# wm8510-dev-board.net
KiCad netlist of a schematic drawn in EAGLE
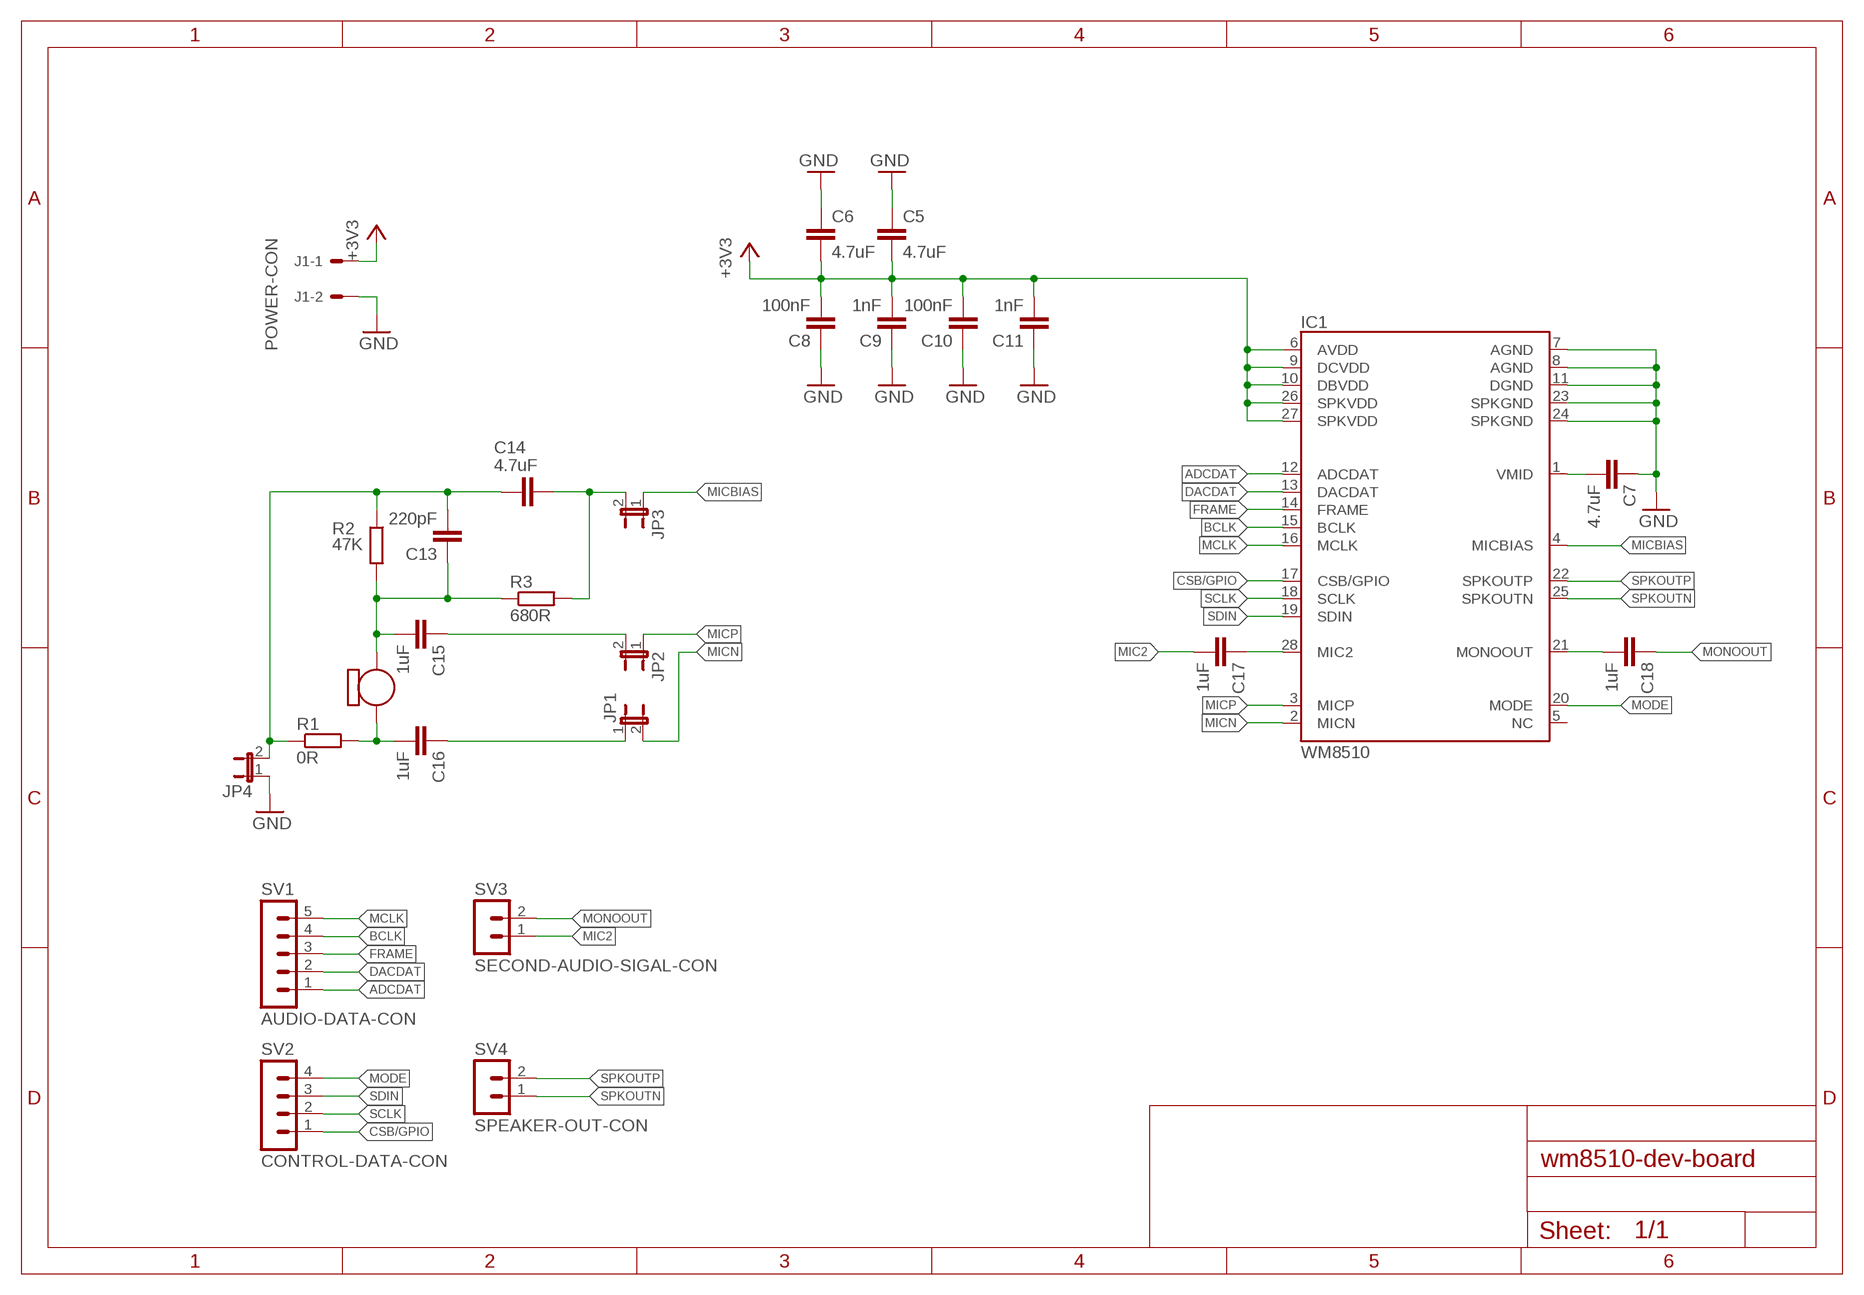
[diagram p0: schematic, sheet 1]

(export (version "E")
  (design (tool "Eeschema 10.0.6"))
  (components
    (comp (ref "C5")
      (value "4.7uF")
      (footprint "eagle-import:C1206")
      (libsource (lib "eagle-import") (part "C-EUC1206"))
    )
    (comp (ref "C6")
      (value "4.7uF")
      (footprint "eagle-import:C1206")
      (libsource (lib "eagle-import") (part "C-EUC1206"))
    )
    (comp (ref "C7")
      (value "4.7uF")
      (footprint "eagle-import:C1206")
      (libsource (lib "eagle-import") (part "C-EUC1206"))
    )
    (comp (ref "C8")
      (value "100nF")
      (footprint "eagle-import:C1206")
      (libsource (lib "eagle-import") (part "C-EUC1206"))
    )
    (comp (ref "C9")
      (value "1nF")
      (footprint "eagle-import:C1206")
      (libsource (lib "eagle-import") (part "C-EUC1206"))
    )
    (comp (ref "C10")
      (value "100nF")
      (footprint "eagle-import:C1206")
      (libsource (lib "eagle-import") (part "C-EUC1206"))
    )
    (comp (ref "C11")
      (value "1nF")
      (footprint "eagle-import:C1206")
      (libsource (lib "eagle-import") (part "C-EUC1206"))
    )
    (comp (ref "C13")
      (value "220pF")
      (footprint "eagle-import:C1206")
      (libsource (lib "eagle-import") (part "C-EUC1206"))
    )
    (comp (ref "C14")
      (value "4.7uF")
      (footprint "eagle-import:C1206")
      (libsource (lib "eagle-import") (part "C-EUC1206"))
    )
    (comp (ref "C15")
      (value "1uF")
      (footprint "eagle-import:C1206")
      (libsource (lib "eagle-import") (part "C-EUC1206"))
    )
    (comp (ref "C16")
      (value "1uF")
      (footprint "eagle-import:C1206")
      (libsource (lib "eagle-import") (part "C-EUC1206"))
    )
    (comp (ref "C17")
      (value "1uF")
      (footprint "eagle-import:C1206")
      (libsource (lib "eagle-import") (part "C-EUC1206"))
    )
    (comp (ref "C18")
      (value "1uF")
      (footprint "eagle-import:C1206")
      (libsource (lib "eagle-import") (part "C-EUC1206"))
    )
    (comp (ref "IC1")
      (value "WM8510")
      (footprint "eagle-import:SSOP28")
      (libsource (lib "eagle-import") (part "WM8510"))
    )
    (comp (ref "J1")
      (value "POWER-CON")
      (footprint "eagle-import:6410-02")
      (libsource (lib "eagle-import") (part "22-?-0227-2021"))
    )
    (comp (ref "JP1")
      (value "JP1E")
      (footprint "eagle-import:JP1")
      (libsource (lib "eagle-import") (part "JP1E"))
    )
    (comp (ref "JP2")
      (value "JP1E")
      (footprint "eagle-import:JP1")
      (libsource (lib "eagle-import") (part "JP1E"))
    )
    (comp (ref "JP3")
      (value "JP1E")
      (footprint "eagle-import:JP1")
      (libsource (lib "eagle-import") (part "JP1E"))
    )
    (comp (ref "JP4")
      (value "JP1E")
      (footprint "eagle-import:JP1")
      (libsource (lib "eagle-import") (part "JP1E"))
    )
    (comp (ref "R1")
      (value "0R")
      (footprint "eagle-import:R1206")
      (libsource (lib "eagle-import") (part "R-EU_R1206"))
    )
    (comp (ref "R2")
      (value "47K")
      (footprint "eagle-import:R1206")
      (libsource (lib "eagle-import") (part "R-EU_R1206"))
    )
    (comp (ref "R3")
      (value "680R")
      (footprint "eagle-import:R1206")
      (libsource (lib "eagle-import") (part "R-EU_R1206"))
    )
    (comp (ref "SV1")
      (value "AUDIO-DATA-CON")
      (footprint "eagle-import:MA05-1")
      (libsource (lib "eagle-import") (part "MA05-1"))
    )
    (comp (ref "SV2")
      (value "CONTROL-DATA-CON")
      (footprint "eagle-import:MA04-1")
      (libsource (lib "eagle-import") (part "MA04-1"))
    )
    (comp (ref "SV3")
      (value "SECOND-AUDIO-SIGAL-CON")
      (footprint "eagle-import:MA03-1")
      (libsource (lib "eagle-import") (part "MA03-1"))
    )
    (comp (ref "SV4")
      (value "SPEAKER-OUT-CON")
      (footprint "eagle-import:MA03-1")
      (libsource (lib "eagle-import") (part "MA03-1"))
    )
    (comp (ref "U$2")
      (value "ABM-707-RC")
      (footprint "eagle-import:ABM-707-RC")
      (libsource (lib "eagle-import") (part "ABM-707-RC"))
    )
  )
  (nets
    (net (code "1") (name "+3V3") (class "Default")
      (node (ref "C10") (pin "2") (pinfunction "2_2") (pintype "passive"))
      (node (ref "C11") (pin "2") (pinfunction "2_2") (pintype "passive"))
      (node (ref "C5") (pin "2") (pinfunction "2_2") (pintype "passive"))
      (node (ref "C6") (pin "2") (pinfunction "2_2") (pintype "passive"))
      (node (ref "C8") (pin "2") (pinfunction "2_2") (pintype "passive"))
      (node (ref "C9") (pin "2") (pinfunction "2_2") (pintype "passive"))
      (node (ref "IC1") (pin "10") (pinfunction "DBVDD_10") (pintype "power_in"))
      (node (ref "IC1") (pin "26") (pinfunction "SPKVDD_26") (pintype "power_in"))
      (node (ref "IC1") (pin "27") (pinfunction "SPKVDD_27") (pintype "power_in"))
      (node (ref "IC1") (pin "6") (pinfunction "AVDD_6") (pintype "power_in"))
      (node (ref "IC1") (pin "9") (pinfunction "DCVDD_9") (pintype "power_in"))
      (node (ref "J1") (pin "1") (pinfunction "S_1") (pintype "passive"))
    )
    (net (code "2") (name "ADCDAT") (class "Default")
      (node (ref "IC1") (pin "12") (pinfunction "ADCDAT_12") (pintype "output"))
      (node (ref "SV1") (pin "1") (pinfunction "1_1") (pintype "passive"))
    )
    (net (code "3") (name "BCLK") (class "Default")
      (node (ref "IC1") (pin "15") (pinfunction "BCLK_15") (pintype "bidirectional"))
      (node (ref "SV1") (pin "4") (pinfunction "4_4") (pintype "passive"))
    )
    (net (code "4") (name "CSB{slash}GPIO") (class "Default")
      (node (ref "IC1") (pin "17") (pinfunction "CSB/GPIO_17") (pintype "bidirectional"))
      (node (ref "SV2") (pin "1") (pinfunction "1_1") (pintype "passive"))
    )
    (net (code "5") (name "DACDAT") (class "Default")
      (node (ref "IC1") (pin "13") (pinfunction "DACDAT_13") (pintype "input"))
      (node (ref "SV1") (pin "2") (pinfunction "2_2") (pintype "passive"))
    )
    (net (code "6") (name "FRAME") (class "Default")
      (node (ref "IC1") (pin "14") (pinfunction "FRAME_14") (pintype "bidirectional"))
      (node (ref "SV1") (pin "3") (pinfunction "3_3") (pintype "passive"))
    )
    (net (code "7") (name "GND") (class "Default")
      (node (ref "C10") (pin "1") (pinfunction "1_1") (pintype "passive"))
      (node (ref "C11") (pin "1") (pinfunction "1_1") (pintype "passive"))
      (node (ref "C5") (pin "1") (pinfunction "1_1") (pintype "passive"))
      (node (ref "C6") (pin "1") (pinfunction "1_1") (pintype "passive"))
      (node (ref "C7") (pin "1") (pinfunction "1_1") (pintype "passive"))
      (node (ref "C8") (pin "1") (pinfunction "1_1") (pintype "passive"))
      (node (ref "C9") (pin "1") (pinfunction "1_1") (pintype "passive"))
      (node (ref "IC1") (pin "11") (pinfunction "DGND_11") (pintype "power_in"))
      (node (ref "IC1") (pin "23") (pinfunction "SPKGND_23") (pintype "power_in"))
      (node (ref "IC1") (pin "24") (pinfunction "SPKGND_24") (pintype "power_in"))
      (node (ref "IC1") (pin "7") (pinfunction "AGND_7") (pintype "power_in"))
      (node (ref "IC1") (pin "8") (pinfunction "AGND_8") (pintype "power_in"))
      (node (ref "J1") (pin "2") (pinfunction "S_2") (pintype "passive"))
      (node (ref "JP4") (pin "1") (pinfunction "1_1") (pintype "passive"))
    )
    (net (code "8") (name "MCLK") (class "Default")
      (node (ref "IC1") (pin "16") (pinfunction "MCLK_16") (pintype "input"))
      (node (ref "SV1") (pin "5") (pinfunction "5_5") (pintype "passive"))
    )
    (net (code "9") (name "MIC2") (class "Default")
      (node (ref "C17") (pin "2") (pinfunction "2_2") (pintype "passive"))
      (node (ref "SV3") (pin "1") (pinfunction "1_1") (pintype "passive"))
    )
    (net (code "10") (name "MICBIAS") (class "Default")
      (node (ref "IC1") (pin "4") (pinfunction "MICBIAS_4") (pintype "bidirectional"))
      (node (ref "JP3") (pin "1") (pinfunction "1_1") (pintype "passive"))
    )
    (net (code "11") (name "MICN") (class "Default")
      (node (ref "IC1") (pin "2") (pinfunction "MICN_2") (pintype "bidirectional"))
      (node (ref "JP1") (pin "2") (pinfunction "2_2") (pintype "passive"))
    )
    (net (code "12") (name "MICP") (class "Default")
      (node (ref "IC1") (pin "3") (pinfunction "MICP_3") (pintype "bidirectional"))
      (node (ref "JP2") (pin "1") (pinfunction "1_1") (pintype "passive"))
    )
    (net (code "13") (name "MODE") (class "Default")
      (node (ref "IC1") (pin "20") (pinfunction "MODE_20") (pintype "bidirectional"))
      (node (ref "SV2") (pin "4") (pinfunction "4_4") (pintype "passive"))
    )
    (net (code "14") (name "MONOOUT") (class "Default")
      (node (ref "C18") (pin "1") (pinfunction "1_1") (pintype "passive"))
      (node (ref "SV3") (pin "2") (pinfunction "2_2") (pintype "passive"))
    )
    (net (code "15") (name "Net-(C13-Pad1)") (class "Default")
      (node (ref "C13") (pin "1") (pinfunction "1_1") (pintype "passive"))
      (node (ref "C15") (pin "2") (pinfunction "2_2") (pintype "passive"))
      (node (ref "R2") (pin "2") (pinfunction "2_2") (pintype "passive"))
      (node (ref "R3") (pin "1") (pinfunction "1_1") (pintype "passive"))
      (node (ref "U$2") (pin "P$1") (pinfunction "P$1_P$1") (pintype "bidirectional"))
    )
    (net (code "16") (name "Net-(C13-Pad2)") (class "Default")
      (node (ref "C13") (pin "2") (pinfunction "2_2") (pintype "passive"))
      (node (ref "C14") (pin "2") (pinfunction "2_2") (pintype "passive"))
      (node (ref "JP4") (pin "2") (pinfunction "2_2") (pintype "passive"))
      (node (ref "R1") (pin "1") (pinfunction "1_1") (pintype "passive"))
      (node (ref "R2") (pin "1") (pinfunction "1_1") (pintype "passive"))
    )
    (net (code "17") (name "Net-(C14-Pad1)") (class "Default")
      (node (ref "C14") (pin "1") (pinfunction "1_1") (pintype "passive"))
      (node (ref "JP3") (pin "2") (pinfunction "2_2") (pintype "passive"))
      (node (ref "R3") (pin "2") (pinfunction "2_2") (pintype "passive"))
    )
    (net (code "18") (name "Net-(C15-Pad1)") (class "Default")
      (node (ref "C15") (pin "1") (pinfunction "1_1") (pintype "passive"))
      (node (ref "JP2") (pin "2") (pinfunction "2_2") (pintype "passive"))
    )
    (net (code "19") (name "Net-(C16-Pad1)") (class "Default")
      (node (ref "C16") (pin "1") (pinfunction "1_1") (pintype "passive"))
      (node (ref "JP1") (pin "1") (pinfunction "1_1") (pintype "passive"))
    )
    (net (code "20") (name "Net-(C16-Pad2)") (class "Default")
      (node (ref "C16") (pin "2") (pinfunction "2_2") (pintype "passive"))
      (node (ref "R1") (pin "2") (pinfunction "2_2") (pintype "passive"))
      (node (ref "U$2") (pin "P$2") (pinfunction "P$2_P$2") (pintype "bidirectional"))
    )
    (net (code "21") (name "Net-(IC1-MIC2)") (class "Default")
      (node (ref "C17") (pin "1") (pinfunction "1_1") (pintype "passive"))
      (node (ref "IC1") (pin "28") (pinfunction "MIC2_28") (pintype "input"))
    )
    (net (code "22") (name "Net-(IC1-MONOOUT)") (class "Default")
      (node (ref "C18") (pin "2") (pinfunction "2_2") (pintype "passive"))
      (node (ref "IC1") (pin "21") (pinfunction "MONOOUT_21") (pintype "output"))
    )
    (net (code "23") (name "Net-(IC1-VMID)") (class "Default")
      (node (ref "C7") (pin "2") (pinfunction "2_2") (pintype "passive"))
      (node (ref "IC1") (pin "1") (pinfunction "VMID_1") (pintype "bidirectional"))
    )
    (net (code "24") (name "SCLK") (class "Default")
      (node (ref "IC1") (pin "18") (pinfunction "SCLK_18") (pintype "input"))
      (node (ref "SV2") (pin "2") (pinfunction "2_2") (pintype "passive"))
    )
    (net (code "25") (name "SDIN") (class "Default")
      (node (ref "IC1") (pin "19") (pinfunction "SDIN_19") (pintype "bidirectional"))
      (node (ref "SV2") (pin "3") (pinfunction "3_3") (pintype "passive"))
    )
    (net (code "26") (name "SPKOUTN") (class "Default")
      (node (ref "IC1") (pin "25") (pinfunction "SPKOUTN_25") (pintype "bidirectional"))
      (node (ref "SV4") (pin "1") (pinfunction "1_1") (pintype "passive"))
    )
    (net (code "27") (name "SPKOUTP") (class "Default")
      (node (ref "IC1") (pin "22") (pinfunction "SPKOUTP_22") (pintype "bidirectional"))
      (node (ref "SV4") (pin "2") (pinfunction "2_2") (pintype "passive"))
    )
    (net (code "28") (name "unconnected-(IC1-NC-Pad5)") (class "Default")
      (node (ref "IC1") (pin "5") (pinfunction "NC_5") (pintype "no_connect"))
    )
  )
)
